# SHTC3_Breakout.net
KiCad netlist of a schematic drawn in EAGLE
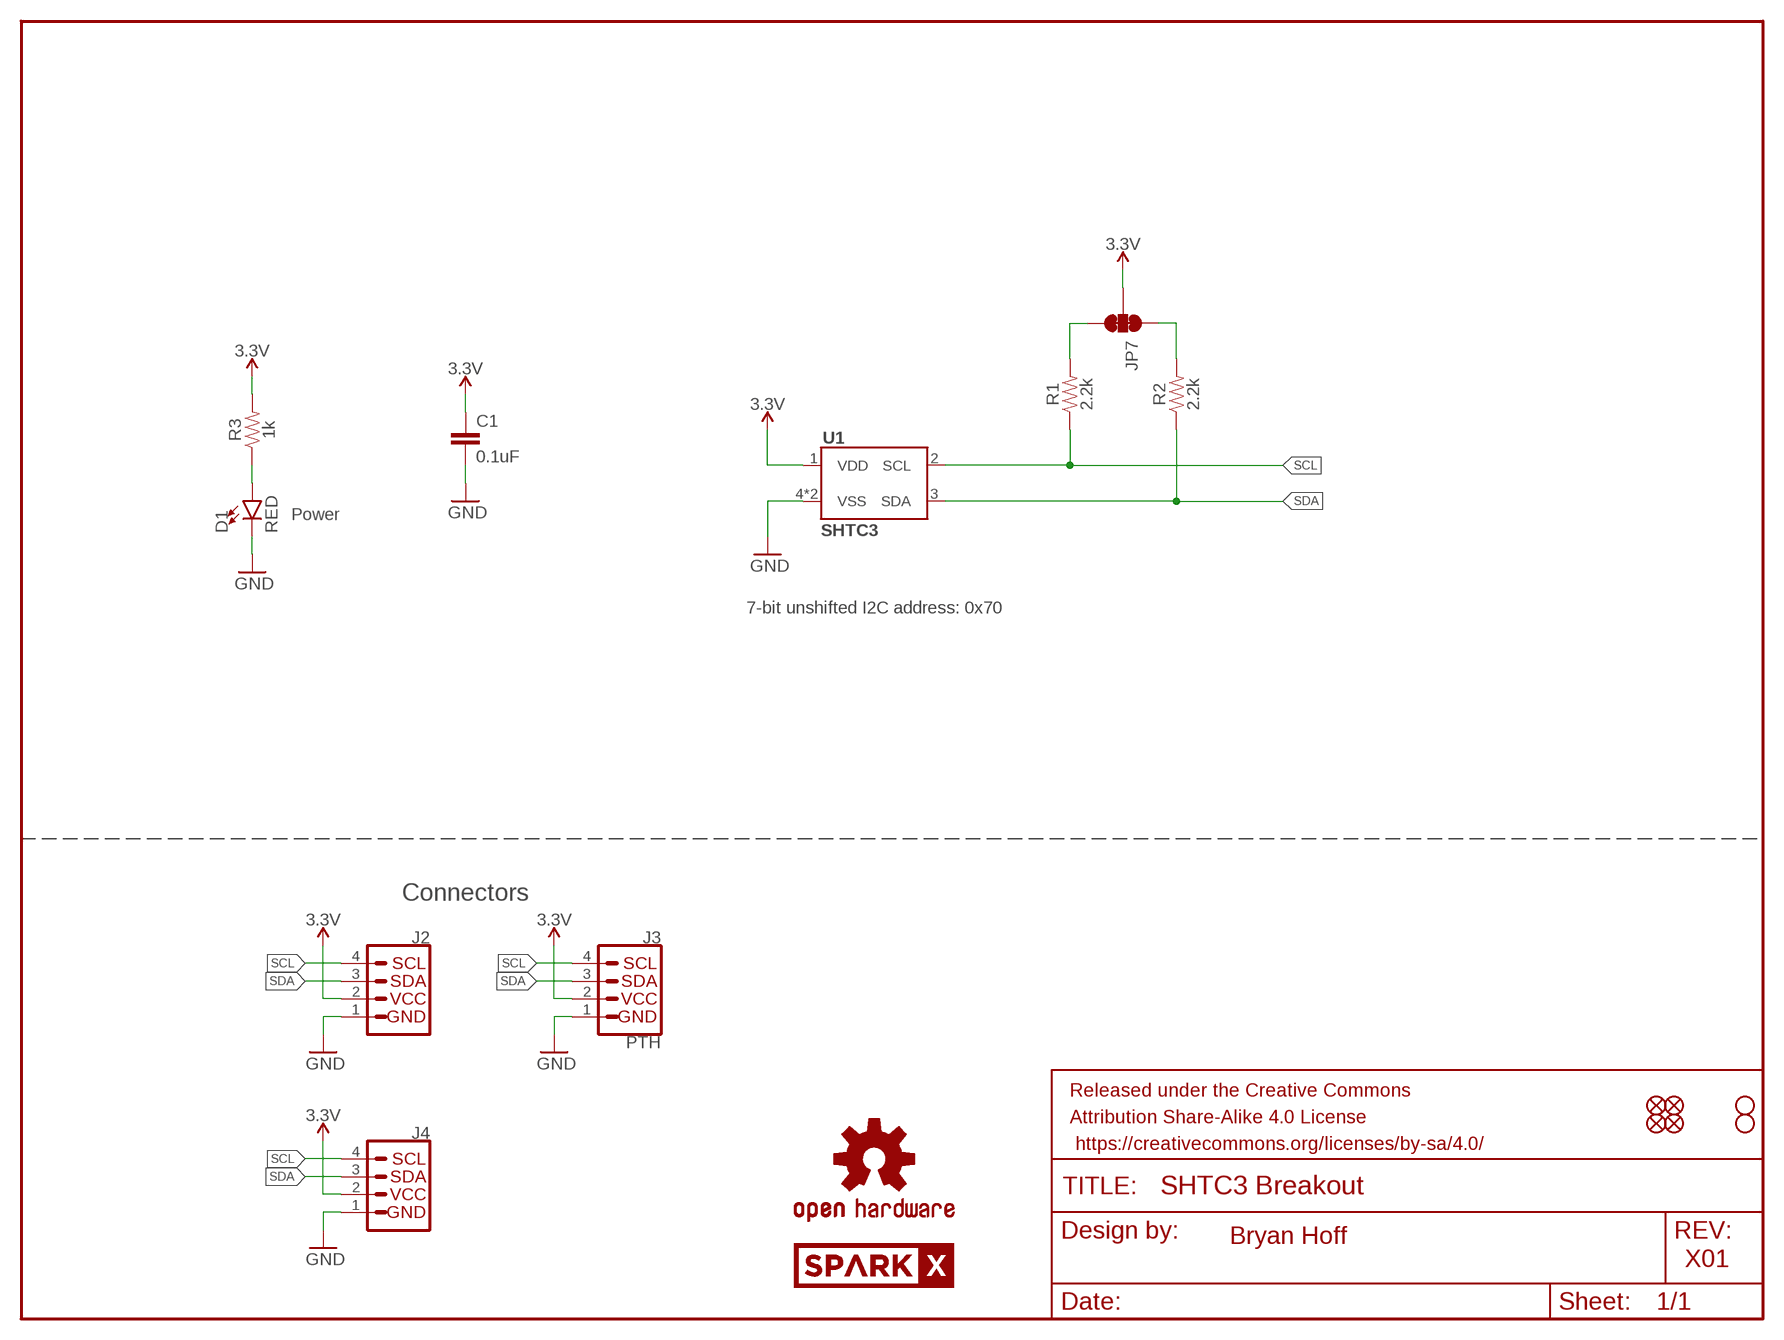
[diagram p0: schematic, sheet 1]

(export (version "E")
  (design (tool "Eeschema 10.0.6"))
  (components
    (comp (ref "C1")
      (value "0.1uF")
      (footprint "eagle-import:0603")
      (libsource (lib "eagle-import") (part "0.1UF-0603-25V-(+80/-20%)"))
    )
    (comp (ref "D1")
      (value "RED")
      (footprint "eagle-import:LED-0603")
      (libsource (lib "eagle-import") (part "LED-RED0603"))
    )
    (comp (ref "FRAME1")
      (value "FRAME-LETTER")
      (footprint "eagle-import:CREATIVE_COMMONS")
      (libsource (lib "eagle-import") (part "FRAME-LETTER"))
    )
    (comp (ref "J2")
      (value "QWIIC_CONNECTORJS-1MM")
      (footprint "eagle-import:1X04_1MM_RA")
      (libsource (lib "eagle-import") (part "QWIIC_CONNECTORJS-1MM"))
    )
    (comp (ref "J3")
      (value "PTH")
      (footprint "eagle-import:1X04_NO_SILK")
      (libsource (lib "eagle-import") (part "I2C_STANDARD_NO_SILK"))
    )
    (comp (ref "J4")
      (value "QWIIC_CONNECTORJS-1MM")
      (footprint "eagle-import:1X04_1MM_RA")
      (libsource (lib "eagle-import") (part "QWIIC_CONNECTORJS-1MM"))
    )
    (comp (ref "JP1")
      (value "FIDUCIALUFIDUCIAL")
      (footprint "eagle-import:MICRO-FIDUCIAL")
      (libsource (lib "eagle-import") (part "FIDUCIALUFIDUCIAL"))
    )
    (comp (ref "JP2")
      (value "FIDUCIALUFIDUCIAL")
      (footprint "eagle-import:MICRO-FIDUCIAL")
      (libsource (lib "eagle-import") (part "FIDUCIALUFIDUCIAL"))
    )
    (comp (ref "JP3")
      (value "STAND-OFF")
      (footprint "eagle-import:STAND-OFF")
      (libsource (lib "eagle-import") (part "STAND-OFF"))
    )
    (comp (ref "JP4")
      (value "STAND-OFF")
      (footprint "eagle-import:STAND-OFF")
      (libsource (lib "eagle-import") (part "STAND-OFF"))
    )
    (comp (ref "JP5")
      (value "FIDUCIALUFIDUCIAL")
      (footprint "eagle-import:MICRO-FIDUCIAL")
      (libsource (lib "eagle-import") (part "FIDUCIALUFIDUCIAL"))
    )
    (comp (ref "JP6")
      (value "FIDUCIALUFIDUCIAL")
      (footprint "eagle-import:MICRO-FIDUCIAL")
      (libsource (lib "eagle-import") (part "FIDUCIALUFIDUCIAL"))
    )
    (comp (ref "JP7")
      (value "JUMPER-SMT_3_2-NC_TRACE_SILK")
      (footprint "eagle-import:SMT-JUMPER_3_2-NC_TRACE_SILK")
      (libsource (lib "eagle-import") (part "JUMPER-SMT_3_2-NC_TRACE_SILK"))
    )
    (comp (ref "LOGO1")
      (value "OSHW-LOGOMINI")
      (footprint "eagle-import:OSHW-LOGO-MINI")
      (libsource (lib "eagle-import") (part "OSHW-LOGOMINI"))
    )
    (comp (ref "R1")
      (value "2.2k")
      (footprint "eagle-import:0603")
      (libsource (lib "eagle-import") (part "2.2KOHM-0603-1/10W-1%"))
    )
    (comp (ref "R2")
      (value "2.2k")
      (footprint "eagle-import:0603")
      (libsource (lib "eagle-import") (part "2.2KOHM-0603-1/10W-1%"))
    )
    (comp (ref "R3")
      (value "1k")
      (footprint "eagle-import:0603")
      (libsource (lib "eagle-import") (part "1KOHM-0603-1/10W-1%"))
    )
    (comp (ref "U$1")
      (value "SPARKX-LOGO4")
      (footprint "eagle-import:SPARKX-MEDIUM")
      (libsource (lib "eagle-import") (part "SPARKX-LOGO4"))
    )
    (comp (ref "U$2")
      (value "SPARKX-LOGO4")
      (footprint "eagle-import:SPARKX-MEDIUM")
      (libsource (lib "eagle-import") (part "SPARKX-LOGO4"))
    )
    (comp (ref "U1")
      (value "SHTC3")
      (footprint "eagle-import:SHTC3")
      (libsource (lib "eagle-import") (part "SHTC3"))
    )
  )
  (nets
    (net (code "1") (name "3.3V") (class "Default")
      (node (ref "C1") (pin "1") (pinfunction "1_1") (pintype "passive"))
      (node (ref "J2") (pin "2") (pinfunction "2_2") (pintype "power_in"))
      (node (ref "J3") (pin "2") (pinfunction "VCC_2") (pintype "power_in"))
      (node (ref "J4") (pin "2") (pinfunction "2_2") (pintype "power_in"))
      (node (ref "JP7") (pin "2") (pinfunction "2_2") (pintype "passive"))
      (node (ref "R3") (pin "2") (pinfunction "2_2") (pintype "passive"))
      (node (ref "U1") (pin "1") (pinfunction "VDD_1") (pintype "bidirectional"))
    )
    (net (code "2") (name "GND") (class "Default")
      (node (ref "C1") (pin "2") (pinfunction "2_2") (pintype "passive"))
      (node (ref "D1") (pin "C") (pinfunction "C_C") (pintype "passive"))
      (node (ref "J2") (pin "1") (pinfunction "1_1") (pintype "power_in"))
      (node (ref "J3") (pin "1") (pinfunction "GND_1") (pintype "power_in"))
      (node (ref "J4") (pin "1") (pinfunction "1_1") (pintype "power_in"))
      (node (ref "U1") (pin "4") (pinfunction "VSS_4") (pintype "bidirectional"))
      (node (ref "U1") (pin "5") (pinfunction "VSS_5") (pintype "bidirectional"))
    )
    (net (code "3") (name "Net-(D1-PadA)") (class "Default")
      (node (ref "D1") (pin "A") (pinfunction "A_A") (pintype "passive"))
      (node (ref "R3") (pin "1") (pinfunction "1_1") (pintype "passive"))
    )
    (net (code "4") (name "Net-(JP7-Pad1)") (class "Default")
      (node (ref "JP7") (pin "1") (pinfunction "1_1") (pintype "passive"))
      (node (ref "R2") (pin "2") (pinfunction "2_2") (pintype "passive"))
    )
    (net (code "5") (name "Net-(JP7-Pad3)") (class "Default")
      (node (ref "JP7") (pin "3") (pinfunction "3_3") (pintype "passive"))
      (node (ref "R1") (pin "2") (pinfunction "2_2") (pintype "passive"))
    )
    (net (code "6") (name "SCL") (class "Default")
      (node (ref "J2") (pin "4") (pinfunction "4_4") (pintype "passive"))
      (node (ref "J3") (pin "4") (pinfunction "SCL_4") (pintype "passive"))
      (node (ref "J4") (pin "4") (pinfunction "4_4") (pintype "passive"))
      (node (ref "R1") (pin "1") (pinfunction "1_1") (pintype "passive"))
      (node (ref "U1") (pin "2") (pinfunction "SCL_2") (pintype "bidirectional"))
    )
    (net (code "7") (name "SDA") (class "Default")
      (node (ref "J2") (pin "3") (pinfunction "3_3") (pintype "passive"))
      (node (ref "J3") (pin "3") (pinfunction "SDA_3") (pintype "passive"))
      (node (ref "J4") (pin "3") (pinfunction "3_3") (pintype "passive"))
      (node (ref "R2") (pin "1") (pinfunction "1_1") (pintype "passive"))
      (node (ref "U1") (pin "3") (pinfunction "SDA_3") (pintype "bidirectional"))
    )
  )
)
